# SSCS_Shematics.net
KiCad netlist of a schematic drawn in Altium Designer
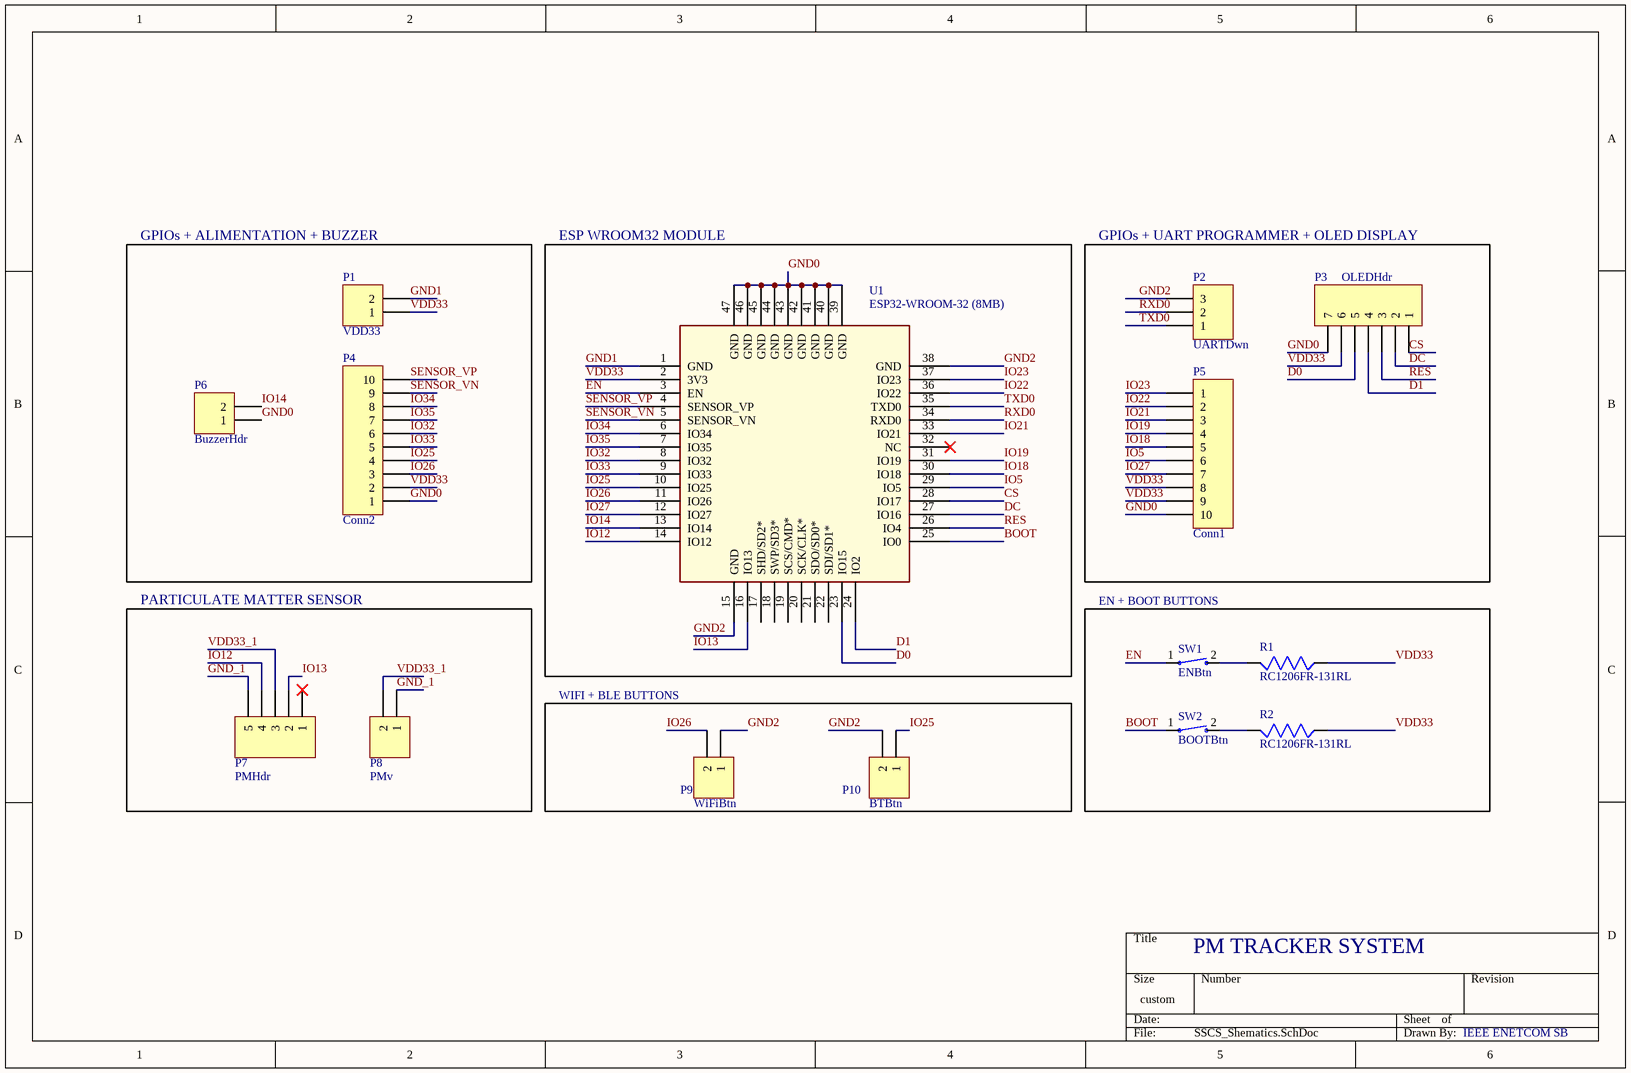
[diagram p0: SSCS_Shematics.SchDoc]

(export (version "E")
  (design (tool "Eeschema 10.0.6"))
  (components
    (comp (ref "P1")
      (value "VDD33")
      (footprint "Conn2x2.54:Conn2x2.54")
      (description "Header, 2-Pin")
      (fields (field (name "PUBLISHER") "Altium Limited"))
      (libsource (lib "") (part "MHDR1X2_1"))
    )
    (comp (ref "P2")
      (value "UARTDwn")
      (footprint "Conn3x2.54:Conn3x2.54")
      (description "Header, 3-Pin")
      (fields (field (name "PUBLISHER") "Altium Limited"))
      (libsource (lib "Miscellaneous Connectors") (part "MHDR1X3"))
    )
    (comp (ref "P3")
      (value "OLEDHdr")
      (footprint "Conn7x2.54:Conn7x2.54")
      (description "Header, 7-Pin")
      (fields (field (name "PUBLISHER") "Altium Limited"))
      (libsource (lib "Miscellaneous Connectors") (part "MHDR1X7"))
    )
    (comp (ref "P4")
      (value "Conn2")
      (footprint "Conn10x2.54:Conn10x2.54")
      (description "Header, 10-Pin")
      (fields (field (name "PUBLISHER") "Altium Limited"))
      (libsource (lib "Miscellaneous Connectors") (part "MHDR1X10"))
    )
    (comp (ref "P5")
      (value "Conn1")
      (footprint "Conn10x2.54:Conn10x2.54")
      (description "Header, 10-Pin")
      (fields (field (name "PUBLISHER") "Altium Limited"))
      (libsource (lib "") (part "MHDR1X10_1"))
    )
    (comp (ref "P6")
      (value "BuzzerHdr")
      (footprint "Conn2x2.54:Conn2x2.54Buzzer")
      (description "Header, 2-Pin")
      (fields (field (name "PUBLISHER") "Altium Limited"))
      (libsource (lib "") (part "MHDR1X2_1"))
    )
    (comp (ref "P7")
      (value "PMHdr")
      (footprint "Conn5x2.54:Conn5x2.54")
      (description "Header, 5-Pin")
      (fields (field (name "PUBLISHER") "Altium Limited"))
      (libsource (lib "Miscellaneous Connectors") (part "MHDR1X5"))
    )
    (comp (ref "P8")
      (value "PMv")
      (footprint "Conn2x2.54:Conn2x2.54")
      (description "Header, 2-Pin")
      (fields (field (name "PUBLISHER") "Altium Limited"))
      (libsource (lib "Miscellaneous Connectors") (part "MHDR1X2"))
    )
    (comp (ref "P9")
      (value "WiFiBtn")
      (footprint "switch:SW")
      (description "Header, 2-Pin")
      (fields (field (name "PUBLISHER") "Altium Limited"))
      (libsource (lib "Miscellaneous Connectors") (part "MHDR1X2"))
    )
    (comp (ref "P10")
      (value "BTBtn")
      (footprint "switch:SW")
      (description "Header, 2-Pin")
      (fields (field (name "PUBLISHER") "Altium Limited"))
      (libsource (lib "Miscellaneous Connectors") (part "MHDR1X2"))
    )
    (comp (ref "R1")
      (value "RC1206FR-131RL")
      (footprint "resistor:res")
      (description "RC Series 1206 0.25 W 0 O Jumper Surface Mount Thick Film Chip Resistor")
      (libsource (lib "resistor") (part "RC1206FR-131RL"))
    )
    (comp (ref "R2")
      (value "RC1206FR-131RL")
      (footprint "resistor:res")
      (description "RC Series 1206 0.25 W 0 O Jumper Surface Mount Thick Film Chip Resistor")
      (libsource (lib "resistor") (part "RC1206FR-131RL"))
    )
    (comp (ref "SW1")
      (value "ENBtn")
      (footprint "switch:SW")
      (description "Switch Tactile OFF (ON) SPST Rectangular Button J-Bend 0.05A 24VDC 1.77N SMD T/R")
      (fields (field (name "MF") "TE Connectivity") (field (name "MP") "147873-1"))
      (libsource (lib "switch") (part "147873-1"))
    )
    (comp (ref "SW2")
      (value "BOOTBtn")
      (footprint "switch:SW")
      (description "Switch Tactile OFF (ON) SPST Rectangular Button J-Bend 0.05A 24VDC 1.77N SMD T/R")
      (fields (field (name "MF") "TE Connectivity") (field (name "MP") "147873-1"))
      (libsource (lib "switch") (part "147873-1"))
    )
    (comp (ref "U1")
      (value "ESP32-WROOM-32 (8MB)")
      (footprint "IC38_ESP32-WROOM-32 8MB_EXP")
      (description "No Description Available")
      (fields (field (name "COPYRIGHT") "Copyright (C) 2023 Ultra Librarian. All rights reserved."))
      (libsource (lib "ESP32-WROOM-328MB") (part "ESP32-WROOM-32 8MB"))
    )
  )
  (nets
    (net (code "1") (name "/BOOT") (class "Default")
      (node (ref "SW2") (pin "1") (pinfunction "1_1") (pintype "passive"))
      (node (ref "U1") (pin "25") (pinfunction "IO0_25") (pintype "passive"))
    )
    (net (code "2") (name "/CS") (class "Default")
      (node (ref "P3") (pin "1") (pinfunction "1_1") (pintype "passive"))
      (node (ref "U1") (pin "28") (pinfunction "IO17_28") (pintype "passive"))
    )
    (net (code "3") (name "/D0") (class "Default")
      (node (ref "P3") (pin "5") (pinfunction "5_5") (pintype "passive"))
      (node (ref "U1") (pin "23") (pinfunction "IO15_23") (pintype "passive"))
    )
    (net (code "4") (name "/D1") (class "Default")
      (node (ref "P3") (pin "4") (pinfunction "4_4") (pintype "passive"))
      (node (ref "U1") (pin "24") (pinfunction "IO2_24") (pintype "passive"))
    )
    (net (code "5") (name "/DC") (class "Default")
      (node (ref "P3") (pin "2") (pinfunction "2_2") (pintype "passive"))
      (node (ref "U1") (pin "27") (pinfunction "IO16_27") (pintype "passive"))
    )
    (net (code "6") (name "/EN") (class "Default")
      (node (ref "SW1") (pin "1") (pinfunction "1_1") (pintype "passive"))
      (node (ref "U1") (pin "3") (pinfunction "EN_3") (pintype "passive"))
    )
    (net (code "7") (name "/GND0") (class "Default")
      (node (ref "P3") (pin "7") (pinfunction "7_7") (pintype "passive"))
      (node (ref "P4") (pin "1") (pinfunction "1_1") (pintype "passive"))
      (node (ref "P5") (pin "10") (pinfunction "10_10") (pintype "passive"))
      (node (ref "P6") (pin "1") (pinfunction "1_1") (pintype "passive"))
      (node (ref "U1") (pin "39") (pinfunction "GND_39") (pintype "passive"))
      (node (ref "U1") (pin "40") (pinfunction "GND_40") (pintype "passive"))
      (node (ref "U1") (pin "41") (pinfunction "GND_41") (pintype "passive"))
      (node (ref "U1") (pin "42") (pinfunction "GND_42") (pintype "passive"))
      (node (ref "U1") (pin "43") (pinfunction "GND_43") (pintype "passive"))
      (node (ref "U1") (pin "44") (pinfunction "GND_44") (pintype "passive"))
      (node (ref "U1") (pin "45") (pinfunction "GND_45") (pintype "passive"))
      (node (ref "U1") (pin "46") (pinfunction "GND_46") (pintype "passive"))
      (node (ref "U1") (pin "47") (pinfunction "GND_47") (pintype "passive"))
    )
    (net (code "8") (name "/GND1") (class "Default")
      (node (ref "P1") (pin "2") (pinfunction "2_2") (pintype "passive"))
      (node (ref "U1") (pin "1") (pinfunction "GND_1") (pintype "passive"))
    )
    (net (code "9") (name "/GND2") (class "Default")
      (node (ref "P10") (pin "2") (pinfunction "2_2") (pintype "passive"))
      (node (ref "P2") (pin "3") (pinfunction "3_3") (pintype "passive"))
      (node (ref "P9") (pin "1") (pinfunction "1_1") (pintype "passive"))
      (node (ref "U1") (pin "15") (pinfunction "GND_15") (pintype "passive"))
      (node (ref "U1") (pin "38") (pinfunction "GND_38") (pintype "passive"))
    )
    (net (code "10") (name "/GND_1") (class "Default")
      (node (ref "P7") (pin "5") (pinfunction "5_5") (pintype "passive"))
      (node (ref "P8") (pin "1") (pinfunction "1_1") (pintype "passive"))
    )
    (net (code "11") (name "/IO5") (class "Default")
      (node (ref "P5") (pin "6") (pinfunction "6_6") (pintype "passive"))
      (node (ref "U1") (pin "29") (pinfunction "IO5_29") (pintype "passive"))
    )
    (net (code "12") (name "/IO12") (class "Default")
      (node (ref "P7") (pin "4") (pinfunction "4_4") (pintype "passive"))
      (node (ref "U1") (pin "14") (pinfunction "IO12_14") (pintype "passive"))
    )
    (net (code "13") (name "/IO13") (class "Default")
      (node (ref "P7") (pin "2") (pinfunction "2_2") (pintype "passive"))
      (node (ref "U1") (pin "16") (pinfunction "IO13_16") (pintype "passive"))
    )
    (net (code "14") (name "/IO14") (class "Default")
      (node (ref "P6") (pin "2") (pinfunction "2_2") (pintype "passive"))
      (node (ref "U1") (pin "13") (pinfunction "IO14_13") (pintype "passive"))
    )
    (net (code "15") (name "/IO18") (class "Default")
      (node (ref "P5") (pin "5") (pinfunction "5_5") (pintype "passive"))
      (node (ref "U1") (pin "30") (pinfunction "IO18_30") (pintype "passive"))
    )
    (net (code "16") (name "/IO19") (class "Default")
      (node (ref "P5") (pin "4") (pinfunction "4_4") (pintype "passive"))
      (node (ref "U1") (pin "31") (pinfunction "IO19_31") (pintype "passive"))
    )
    (net (code "17") (name "/IO21") (class "Default")
      (node (ref "P5") (pin "3") (pinfunction "3_3") (pintype "passive"))
      (node (ref "U1") (pin "33") (pinfunction "IO21_33") (pintype "passive"))
    )
    (net (code "18") (name "/IO22") (class "Default")
      (node (ref "P5") (pin "2") (pinfunction "2_2") (pintype "passive"))
      (node (ref "U1") (pin "36") (pinfunction "IO22_36") (pintype "passive"))
    )
    (net (code "19") (name "/IO23") (class "Default")
      (node (ref "P5") (pin "1") (pinfunction "1_1") (pintype "passive"))
      (node (ref "U1") (pin "37") (pinfunction "IO23_37") (pintype "passive"))
    )
    (net (code "20") (name "/IO25") (class "Default")
      (node (ref "P10") (pin "1") (pinfunction "1_1") (pintype "passive"))
      (node (ref "P4") (pin "4") (pinfunction "4_4") (pintype "passive"))
      (node (ref "U1") (pin "10") (pinfunction "IO25_10") (pintype "passive"))
    )
    (net (code "21") (name "/IO26") (class "Default")
      (node (ref "P4") (pin "3") (pinfunction "3_3") (pintype "passive"))
      (node (ref "P9") (pin "2") (pinfunction "2_2") (pintype "passive"))
      (node (ref "U1") (pin "11") (pinfunction "IO26_11") (pintype "passive"))
    )
    (net (code "22") (name "/IO27") (class "Default")
      (node (ref "P5") (pin "7") (pinfunction "7_7") (pintype "passive"))
      (node (ref "U1") (pin "12") (pinfunction "IO27_12") (pintype "passive"))
    )
    (net (code "23") (name "/IO32") (class "Default")
      (node (ref "P4") (pin "6") (pinfunction "6_6") (pintype "passive"))
      (node (ref "U1") (pin "8") (pinfunction "IO32_8") (pintype "passive"))
    )
    (net (code "24") (name "/IO33") (class "Default")
      (node (ref "P4") (pin "5") (pinfunction "5_5") (pintype "passive"))
      (node (ref "U1") (pin "9") (pinfunction "IO33_9") (pintype "passive"))
    )
    (net (code "25") (name "/IO34") (class "Default")
      (node (ref "P4") (pin "8") (pinfunction "8_8") (pintype "passive"))
      (node (ref "U1") (pin "6") (pinfunction "IO34_6") (pintype "passive"))
    )
    (net (code "26") (name "/IO35") (class "Default")
      (node (ref "P4") (pin "7") (pinfunction "7_7") (pintype "passive"))
      (node (ref "U1") (pin "7") (pinfunction "IO35_7") (pintype "passive"))
    )
    (net (code "27") (name "/RES") (class "Default")
      (node (ref "P3") (pin "3") (pinfunction "3_3") (pintype "passive"))
      (node (ref "U1") (pin "26") (pinfunction "IO4_26") (pintype "passive"))
    )
    (net (code "28") (name "/RXD0") (class "Default")
      (node (ref "P2") (pin "2") (pinfunction "2_2") (pintype "passive"))
      (node (ref "U1") (pin "34") (pinfunction "RXD0_34") (pintype "passive"))
    )
    (net (code "29") (name "/SENSOR_VN") (class "Default")
      (node (ref "P4") (pin "9") (pinfunction "9_9") (pintype "passive"))
      (node (ref "U1") (pin "5") (pinfunction "SENSOR_VN_5") (pintype "passive"))
    )
    (net (code "30") (name "/SENSOR_VP") (class "Default")
      (node (ref "P4") (pin "10") (pinfunction "10_10") (pintype "passive"))
      (node (ref "U1") (pin "4") (pinfunction "SENSOR_VP_4") (pintype "passive"))
    )
    (net (code "31") (name "/TXD0") (class "Default")
      (node (ref "P2") (pin "1") (pinfunction "1_1") (pintype "passive"))
      (node (ref "U1") (pin "35") (pinfunction "TXD0_35") (pintype "passive"))
    )
    (net (code "32") (name "/VDD33") (class "Default")
      (node (ref "P1") (pin "1") (pinfunction "1_1") (pintype "passive"))
      (node (ref "P3") (pin "6") (pinfunction "6_6") (pintype "passive"))
      (node (ref "P4") (pin "2") (pinfunction "2_2") (pintype "passive"))
      (node (ref "P5") (pin "8") (pinfunction "8_8") (pintype "passive"))
      (node (ref "P5") (pin "9") (pinfunction "9_9") (pintype "passive"))
      (node (ref "R1") (pin "2") (pinfunction "2_2") (pintype "passive"))
      (node (ref "R2") (pin "2") (pinfunction "2_2") (pintype "passive"))
      (node (ref "U1") (pin "2") (pinfunction "3V3_2") (pintype "passive"))
    )
    (net (code "33") (name "/VDD33_1") (class "Default")
      (node (ref "P7") (pin "3") (pinfunction "3_3") (pintype "passive"))
      (node (ref "P8") (pin "2") (pinfunction "2_2") (pintype "passive"))
    )
    (net (code "34") (name "Net-(R1-Pad1)") (class "Default")
      (node (ref "R1") (pin "1") (pinfunction "1_1") (pintype "passive"))
      (node (ref "SW1") (pin "2") (pinfunction "2_2") (pintype "passive"))
    )
    (net (code "35") (name "Net-(R2-Pad1)") (class "Default")
      (node (ref "R2") (pin "1") (pinfunction "1_1") (pintype "passive"))
      (node (ref "SW2") (pin "2") (pinfunction "2_2") (pintype "passive"))
    )
    (net (code "36") (name "unconnected-(P7-Pad1)") (class "Default")
      (node (ref "P7") (pin "1") (pinfunction "1_1") (pintype "passive+no_connect"))
    )
    (net (code "37") (name "unconnected-(U1-NC-Pad32)") (class "Default")
      (node (ref "U1") (pin "32") (pinfunction "NC_32") (pintype "passive+no_connect"))
    )
    (net (code "38") (name "unconnected-(U1-SCK{slash}CLK*-Pad20)") (class "Default")
      (node (ref "U1") (pin "20") (pinfunction "SCK/CLK*_20") (pintype "passive"))
    )
    (net (code "39") (name "unconnected-(U1-SCS{slash}CMD*-Pad19)") (class "Default")
      (node (ref "U1") (pin "19") (pinfunction "SCS/CMD*_19") (pintype "passive"))
    )
    (net (code "40") (name "unconnected-(U1-SDI{slash}SD1*-Pad22)") (class "Default")
      (node (ref "U1") (pin "22") (pinfunction "SDI/SD1*_22") (pintype "passive"))
    )
    (net (code "41") (name "unconnected-(U1-SDO{slash}SD0*-Pad21)") (class "Default")
      (node (ref "U1") (pin "21") (pinfunction "SDO/SD0*_21") (pintype "passive"))
    )
    (net (code "42") (name "unconnected-(U1-SHD{slash}SD2*-Pad17)") (class "Default")
      (node (ref "U1") (pin "17") (pinfunction "SHD/SD2*_17") (pintype "passive"))
    )
    (net (code "43") (name "unconnected-(U1-SWP{slash}SD3*-Pad18)") (class "Default")
      (node (ref "U1") (pin "18") (pinfunction "SWP/SD3*_18") (pintype "passive"))
    )
  )
)
